# 12V_Analog_Controller.net
KiCad netlist of a schematic drawn in EAGLE
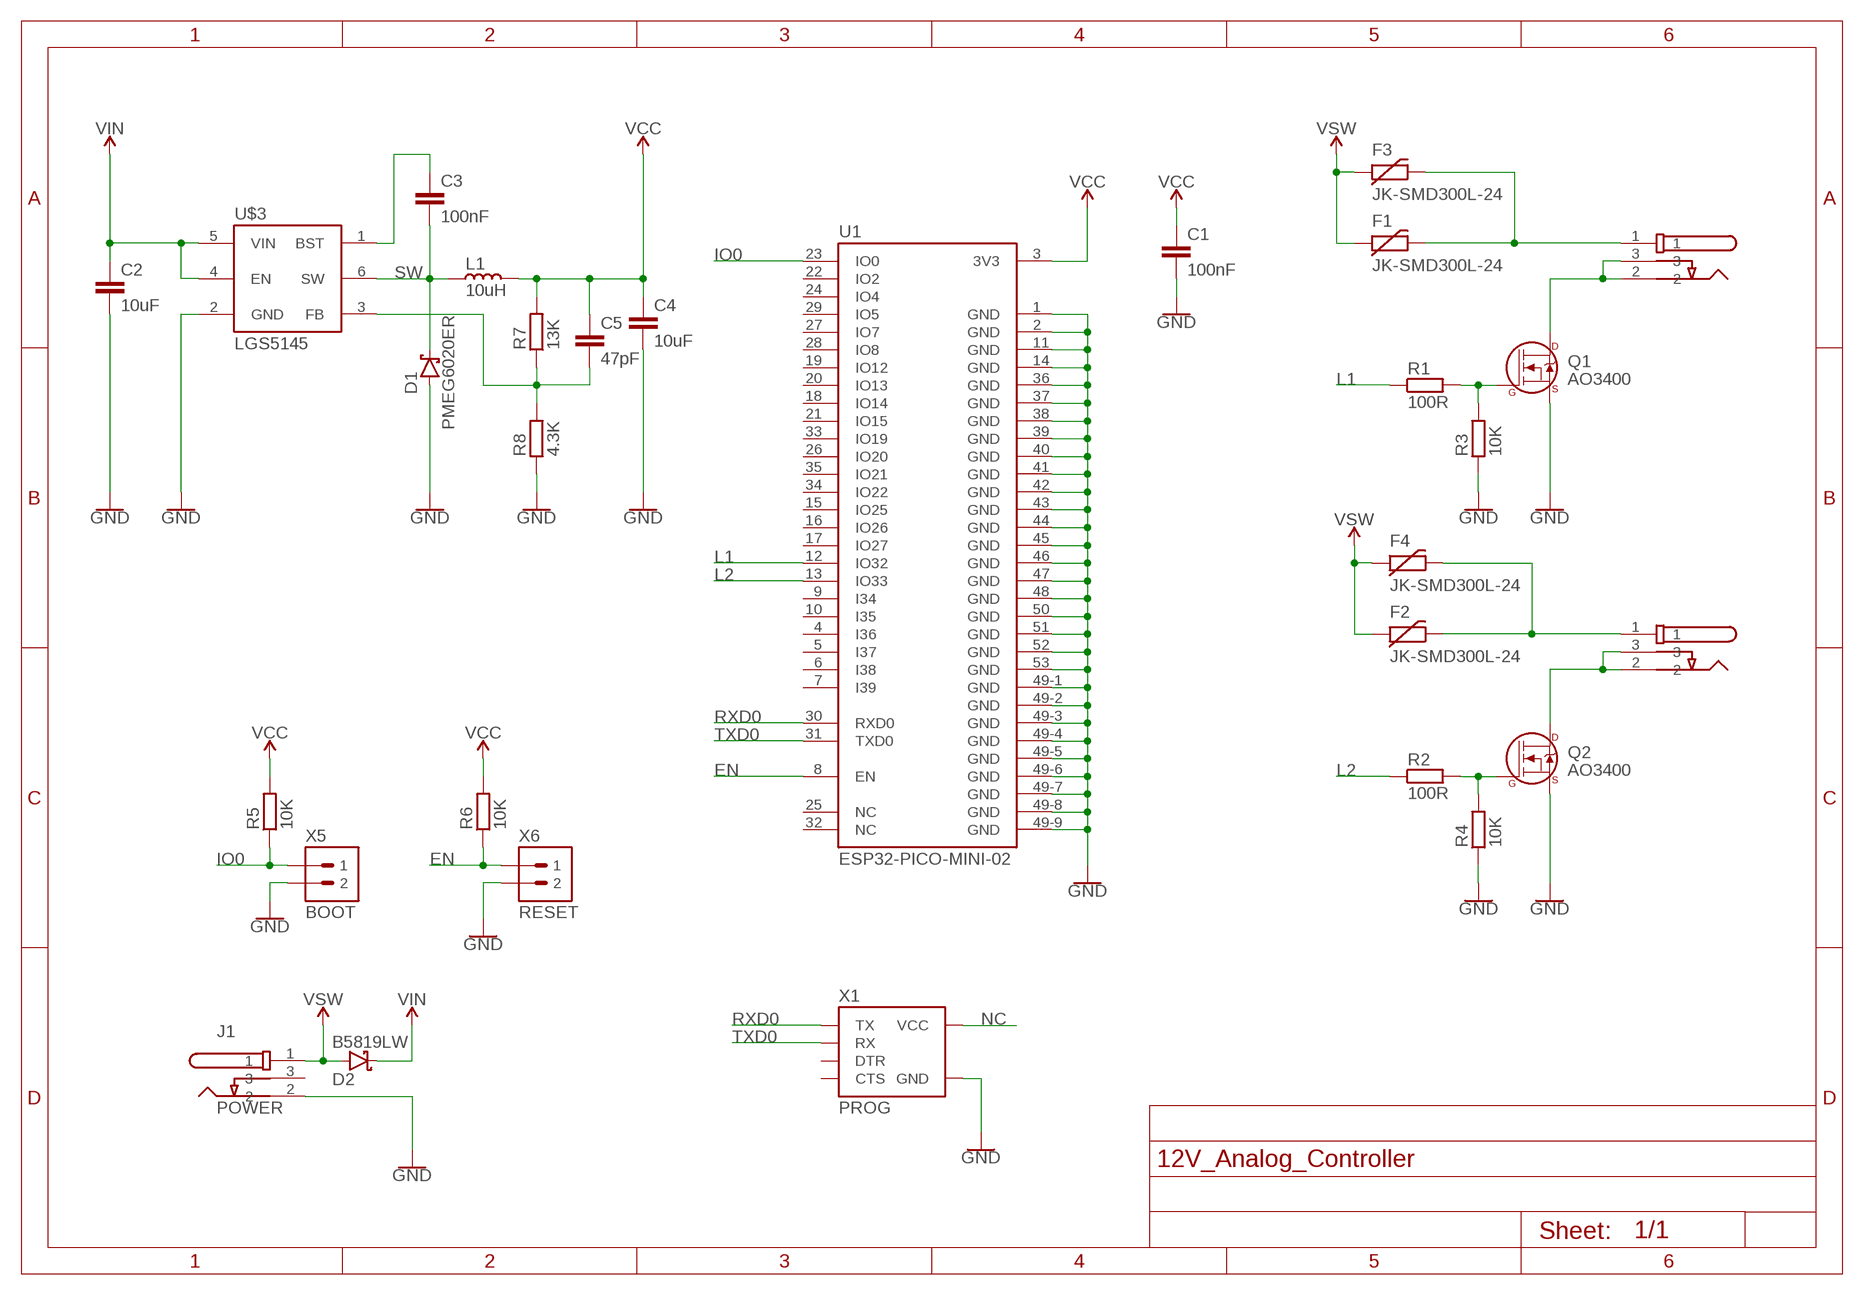
[diagram p0: schematic, sheet 1]

(export (version "E")
  (design (tool "Eeschema 10.0.6"))
  (components
    (comp (ref "C1")
      (value "100nF")
      (footprint "eagle-import:C0603")
      (libsource (lib "eagle-import") (part "CAPC0603"))
    )
    (comp (ref "C2")
      (value "10uF")
      (footprint "eagle-import:C0603")
      (libsource (lib "eagle-import") (part "CAPC0603"))
    )
    (comp (ref "C3")
      (value "100nF")
      (footprint "eagle-import:C0603")
      (libsource (lib "eagle-import") (part "CAPC0603"))
    )
    (comp (ref "C4")
      (value "10uF")
      (footprint "eagle-import:C0603")
      (libsource (lib "eagle-import") (part "CAPC0603"))
    )
    (comp (ref "C5")
      (value "47pF")
      (footprint "eagle-import:C0603")
      (libsource (lib "eagle-import") (part "CAPC0603"))
    )
    (comp (ref "D1")
      (value "PMEG6020ER")
      (footprint "eagle-import:SOD-123FL")
      (libsource (lib "eagle-import") (part "DIODE-SCHOTTKYSOD123FL"))
    )
    (comp (ref "D2")
      (value "B5819LW")
      (footprint "eagle-import:SOD-123")
      (libsource (lib "eagle-import") (part "DIODE-SCHOTTKYSOD-123"))
    )
    (comp (ref "F1")
      (value "JK-SMD300L-24")
      (footprint "eagle-import:JK-SMD300")
      (libsource (lib "eagle-import") (part "PTCJK-SMD300"))
    )
    (comp (ref "F2")
      (value "JK-SMD300L-24")
      (footprint "eagle-import:JK-SMD300")
      (libsource (lib "eagle-import") (part "PTCJK-SMD300"))
    )
    (comp (ref "F3")
      (value "JK-SMD300L-24")
      (footprint "eagle-import:JK-SMD300")
      (libsource (lib "eagle-import") (part "PTCJK-SMD300"))
    )
    (comp (ref "F4")
      (value "JK-SMD300L-24")
      (footprint "eagle-import:JK-SMD300")
      (libsource (lib "eagle-import") (part "PTCJK-SMD300"))
    )
    (comp (ref "J1")
      (value "POWER")
      (footprint "eagle-import:XKB-DC-005-5A-2.0")
      (libsource (lib "eagle-import") (part "XKB-DC-005-5A-2.0"))
    )
    (comp (ref "L1")
      (value "10uH")
      (footprint "eagle-import:YJYCOIN-YNR4062")
      (libsource (lib "eagle-import") (part "IND-YJYCOIN-YNR4062"))
    )
    (comp (ref "Q1")
      (value "AO3400")
      (footprint "eagle-import:SOT23-3")
      (libsource (lib "eagle-import") (part "MOSFET-NCHSOT23-3"))
    )
    (comp (ref "Q2")
      (value "AO3400")
      (footprint "eagle-import:SOT23-3")
      (libsource (lib "eagle-import") (part "MOSFET-NCHSOT23-3"))
    )
    (comp (ref "R1")
      (value "100R")
      (footprint "eagle-import:R0603")
      (libsource (lib "eagle-import") (part "RESISTOR0603"))
    )
    (comp (ref "R2")
      (value "100R")
      (footprint "eagle-import:R0603")
      (libsource (lib "eagle-import") (part "RESISTOR0603"))
    )
    (comp (ref "R3")
      (value "10K")
      (footprint "eagle-import:R0603")
      (libsource (lib "eagle-import") (part "RESISTOR0603"))
    )
    (comp (ref "R4")
      (value "10K")
      (footprint "eagle-import:R0603")
      (libsource (lib "eagle-import") (part "RESISTOR0603"))
    )
    (comp (ref "R5")
      (value "10K")
      (footprint "eagle-import:R0603")
      (libsource (lib "eagle-import") (part "RESISTOR0603"))
    )
    (comp (ref "R6")
      (value "10K")
      (footprint "eagle-import:R0603")
      (libsource (lib "eagle-import") (part "RESISTOR0603"))
    )
    (comp (ref "R7")
      (value "13K")
      (footprint "eagle-import:R0603")
      (libsource (lib "eagle-import") (part "RESISTOR0603"))
    )
    (comp (ref "R8")
      (value "4.3K")
      (footprint "eagle-import:R0603")
      (libsource (lib "eagle-import") (part "RESISTOR0603"))
    )
    (comp (ref "U$3")
      (value "LGS5145")
      (footprint "eagle-import:SOT23-6")
      (libsource (lib "eagle-import") (part "LEGEND-SI-LGS5145"))
    )
    (comp (ref "U1")
      (value "ESP32-PICO-MINI-02")
      (footprint "eagle-import:ESP32-PICO-MINI-02")
      (libsource (lib "eagle-import") (part "ESP32-PICO-MINI-02"))
    )
    (comp (ref "X1")
      (value "PROG")
      (footprint "eagle-import:FTDI232-1X06")
      (libsource (lib "eagle-import") (part "HEADER-FTDI232"))
    )
    (comp (ref "X2")
      (value "L1")
      (footprint "eagle-import:XKB-DC-005-5A-2.0")
      (libsource (lib "eagle-import") (part "XKB-DC-005-5A-2.0"))
    )
    (comp (ref "X3")
      (value "L2")
      (footprint "eagle-import:XKB-DC-005-5A-2.0")
      (libsource (lib "eagle-import") (part "XKB-DC-005-5A-2.0"))
    )
    (comp (ref "X5")
      (value "BOOT")
      (footprint "eagle-import:1X02-2.54")
      (libsource (lib "eagle-import") (part "HEADER-1X02-2.54"))
    )
    (comp (ref "X6")
      (value "RESET")
      (footprint "eagle-import:1X02-2.54")
      (libsource (lib "eagle-import") (part "HEADER-1X02-2.54"))
    )
  )
  (nets
    (net (code "1") (name "/EN") (class "Default")
      (node (ref "R6") (pin "1") (pinfunction "1_1") (pintype "passive"))
      (node (ref "U1") (pin "8") (pinfunction "EN_8") (pintype "bidirectional"))
      (node (ref "X6") (pin "1") (pinfunction "1_1") (pintype "passive"))
    )
    (net (code "2") (name "/IO0") (class "Default")
      (node (ref "R5") (pin "1") (pinfunction "1_1") (pintype "passive"))
      (node (ref "U1") (pin "23") (pinfunction "IO0_23") (pintype "bidirectional"))
      (node (ref "X5") (pin "1") (pinfunction "1_1") (pintype "passive"))
    )
    (net (code "3") (name "/L1") (class "Default")
      (node (ref "R1") (pin "1") (pinfunction "1_1") (pintype "passive"))
      (node (ref "U1") (pin "12") (pinfunction "IO32_12") (pintype "bidirectional"))
    )
    (net (code "4") (name "/L2") (class "Default")
      (node (ref "R2") (pin "1") (pinfunction "1_1") (pintype "passive"))
      (node (ref "U1") (pin "13") (pinfunction "IO33_13") (pintype "bidirectional"))
    )
    (net (code "5") (name "/NC") (class "Default")
      (node (ref "X1") (pin "VCC") (pinfunction "VCC_VCC") (pintype "power_in"))
    )
    (net (code "6") (name "/RXD0") (class "Default")
      (node (ref "U1") (pin "30") (pinfunction "RXD0_30") (pintype "bidirectional"))
      (node (ref "X1") (pin "TX") (pinfunction "TX_TX") (pintype "output"))
    )
    (net (code "7") (name "/SW") (class "Default")
      (node (ref "C3") (pin "2") (pinfunction "2_2") (pintype "passive"))
      (node (ref "D1") (pin "C") (pinfunction "C_C") (pintype "passive"))
      (node (ref "L1") (pin "1") (pinfunction "1_1") (pintype "passive"))
      (node (ref "U$3") (pin "6") (pinfunction "SW_6") (pintype "bidirectional"))
    )
    (net (code "8") (name "/TXD0") (class "Default")
      (node (ref "U1") (pin "31") (pinfunction "TXD0_31") (pintype "bidirectional"))
      (node (ref "X1") (pin "RX") (pinfunction "RX_RX") (pintype "input"))
    )
    (net (code "9") (name "GND") (class "Default")
      (node (ref "C1") (pin "2") (pinfunction "2_2") (pintype "passive"))
      (node (ref "C2") (pin "2") (pinfunction "2_2") (pintype "passive"))
      (node (ref "C4") (pin "2") (pinfunction "2_2") (pintype "passive"))
      (node (ref "D1") (pin "A") (pinfunction "A_A") (pintype "passive"))
      (node (ref "J1") (pin "2") (pinfunction "2_2") (pintype "bidirectional"))
      (node (ref "Q1") (pin "2") (pinfunction "S_2") (pintype "bidirectional"))
      (node (ref "Q2") (pin "2") (pinfunction "S_2") (pintype "bidirectional"))
      (node (ref "R3") (pin "1") (pinfunction "1_1") (pintype "passive"))
      (node (ref "R4") (pin "1") (pinfunction "1_1") (pintype "passive"))
      (node (ref "R8") (pin "1") (pinfunction "1_1") (pintype "passive"))
      (node (ref "U$3") (pin "2") (pinfunction "GND_2") (pintype "bidirectional"))
      (node (ref "U1") (pin "1") (pinfunction "GND_1") (pintype "bidirectional"))
      (node (ref "U1") (pin "11") (pinfunction "GND_11") (pintype "bidirectional"))
      (node (ref "U1") (pin "14") (pinfunction "GND_14") (pintype "bidirectional"))
      (node (ref "U1") (pin "2") (pinfunction "GND_2") (pintype "bidirectional"))
      (node (ref "U1") (pin "36") (pinfunction "GND_36") (pintype "bidirectional"))
      (node (ref "U1") (pin "37") (pinfunction "GND_37") (pintype "bidirectional"))
      (node (ref "U1") (pin "38") (pinfunction "GND_38") (pintype "bidirectional"))
      (node (ref "U1") (pin "39") (pinfunction "GND_39") (pintype "bidirectional"))
      (node (ref "U1") (pin "40") (pinfunction "GND_40") (pintype "bidirectional"))
      (node (ref "U1") (pin "41") (pinfunction "GND_41") (pintype "bidirectional"))
      (node (ref "U1") (pin "42") (pinfunction "GND_42") (pintype "bidirectional"))
      (node (ref "U1") (pin "43") (pinfunction "GND_43") (pintype "bidirectional"))
      (node (ref "U1") (pin "44") (pinfunction "GND_44") (pintype "bidirectional"))
      (node (ref "U1") (pin "45") (pinfunction "GND_45") (pintype "bidirectional"))
      (node (ref "U1") (pin "46") (pinfunction "GND_46") (pintype "bidirectional"))
      (node (ref "U1") (pin "47") (pinfunction "GND_47") (pintype "bidirectional"))
      (node (ref "U1") (pin "48") (pinfunction "GND_48") (pintype "bidirectional"))
      (node (ref "U1") (pin "49-1") (pinfunction "GND_49-1") (pintype "bidirectional"))
      (node (ref "U1") (pin "49-2") (pinfunction "GND_49-2") (pintype "bidirectional"))
      (node (ref "U1") (pin "49-3") (pinfunction "GND_49-3") (pintype "bidirectional"))
      (node (ref "U1") (pin "49-4") (pinfunction "GND_49-4") (pintype "bidirectional"))
      (node (ref "U1") (pin "49-5") (pinfunction "GND_49-5") (pintype "bidirectional"))
      (node (ref "U1") (pin "49-6") (pinfunction "GND_49-6") (pintype "bidirectional"))
      (node (ref "U1") (pin "49-7") (pinfunction "GND_49-7") (pintype "bidirectional"))
      (node (ref "U1") (pin "49-8") (pinfunction "GND_49-8") (pintype "bidirectional"))
      (node (ref "U1") (pin "49-9") (pinfunction "GND_49-9") (pintype "bidirectional"))
      (node (ref "U1") (pin "50") (pinfunction "GND_50") (pintype "bidirectional"))
      (node (ref "U1") (pin "51") (pinfunction "GND_51") (pintype "bidirectional"))
      (node (ref "U1") (pin "52") (pinfunction "GND_52") (pintype "bidirectional"))
      (node (ref "U1") (pin "53") (pinfunction "GND_53") (pintype "bidirectional"))
      (node (ref "X1") (pin "GND") (pinfunction "GND_GND") (pintype "power_in"))
      (node (ref "X5") (pin "2") (pinfunction "2_2") (pintype "passive"))
      (node (ref "X6") (pin "2") (pinfunction "2_2") (pintype "passive"))
    )
    (net (code "10") (name "Net-(F1-2)") (class "Default")
      (node (ref "F1") (pin "B") (pinfunction "2_B") (pintype "bidirectional"))
      (node (ref "F3") (pin "B") (pinfunction "2_B") (pintype "bidirectional"))
      (node (ref "X2") (pin "1") (pinfunction "1_1") (pintype "bidirectional"))
    )
    (net (code "11") (name "Net-(F2-2)") (class "Default")
      (node (ref "F2") (pin "B") (pinfunction "2_B") (pintype "bidirectional"))
      (node (ref "F4") (pin "B") (pinfunction "2_B") (pintype "bidirectional"))
      (node (ref "X3") (pin "1") (pinfunction "1_1") (pintype "bidirectional"))
    )
    (net (code "12") (name "Net-(Q1-D)") (class "Default")
      (node (ref "Q1") (pin "3") (pinfunction "D_3") (pintype "bidirectional"))
      (node (ref "X2") (pin "2") (pinfunction "2_2") (pintype "bidirectional"))
      (node (ref "X2") (pin "3") (pinfunction "3_3") (pintype "bidirectional"))
    )
    (net (code "13") (name "Net-(Q1-G)") (class "Default")
      (node (ref "Q1") (pin "1") (pinfunction "G_1") (pintype "bidirectional"))
      (node (ref "R1") (pin "2") (pinfunction "2_2") (pintype "passive"))
      (node (ref "R3") (pin "2") (pinfunction "2_2") (pintype "passive"))
    )
    (net (code "14") (name "Net-(Q2-D)") (class "Default")
      (node (ref "Q2") (pin "3") (pinfunction "D_3") (pintype "bidirectional"))
      (node (ref "X3") (pin "2") (pinfunction "2_2") (pintype "bidirectional"))
      (node (ref "X3") (pin "3") (pinfunction "3_3") (pintype "bidirectional"))
    )
    (net (code "15") (name "Net-(Q2-G)") (class "Default")
      (node (ref "Q2") (pin "1") (pinfunction "G_1") (pintype "bidirectional"))
      (node (ref "R2") (pin "2") (pinfunction "2_2") (pintype "passive"))
      (node (ref "R4") (pin "2") (pinfunction "2_2") (pintype "passive"))
    )
    (net (code "16") (name "Net-(U$3-BST)") (class "Default")
      (node (ref "C3") (pin "1") (pinfunction "1_1") (pintype "passive"))
      (node (ref "U$3") (pin "1") (pinfunction "BST_1") (pintype "bidirectional"))
    )
    (net (code "17") (name "Net-(U$3-FB)") (class "Default")
      (node (ref "C5") (pin "2") (pinfunction "2_2") (pintype "passive"))
      (node (ref "R7") (pin "1") (pinfunction "1_1") (pintype "passive"))
      (node (ref "R8") (pin "2") (pinfunction "2_2") (pintype "passive"))
      (node (ref "U$3") (pin "3") (pinfunction "FB_3") (pintype "bidirectional"))
    )
    (net (code "18") (name "VCC") (class "Default")
      (node (ref "C1") (pin "1") (pinfunction "1_1") (pintype "passive"))
      (node (ref "C4") (pin "1") (pinfunction "1_1") (pintype "passive"))
      (node (ref "C5") (pin "1") (pinfunction "1_1") (pintype "passive"))
      (node (ref "L1") (pin "2") (pinfunction "2_2") (pintype "passive"))
      (node (ref "R5") (pin "2") (pinfunction "2_2") (pintype "passive"))
      (node (ref "R6") (pin "2") (pinfunction "2_2") (pintype "passive"))
      (node (ref "R7") (pin "2") (pinfunction "2_2") (pintype "passive"))
      (node (ref "U1") (pin "3") (pinfunction "3V3_3") (pintype "bidirectional"))
    )
    (net (code "19") (name "VIN") (class "Default")
      (node (ref "C2") (pin "1") (pinfunction "1_1") (pintype "passive"))
      (node (ref "D2") (pin "C") (pinfunction "C_C") (pintype "passive"))
      (node (ref "U$3") (pin "4") (pinfunction "EN_4") (pintype "bidirectional"))
      (node (ref "U$3") (pin "5") (pinfunction "VIN_5") (pintype "bidirectional"))
    )
    (net (code "20") (name "VSW") (class "Default")
      (node (ref "D2") (pin "A") (pinfunction "A_A") (pintype "passive"))
      (node (ref "F1") (pin "A") (pinfunction "1_A") (pintype "bidirectional"))
      (node (ref "F2") (pin "A") (pinfunction "1_A") (pintype "bidirectional"))
      (node (ref "F3") (pin "A") (pinfunction "1_A") (pintype "bidirectional"))
      (node (ref "F4") (pin "A") (pinfunction "1_A") (pintype "bidirectional"))
      (node (ref "J1") (pin "1") (pinfunction "1_1") (pintype "bidirectional"))
    )
    (net (code "21") (name "unconnected-(J1-Pad3)") (class "Default")
      (node (ref "J1") (pin "3") (pinfunction "3_3") (pintype "bidirectional"))
    )
    (net (code "22") (name "unconnected-(U1-I34-Pad9)") (class "Default")
      (node (ref "U1") (pin "9") (pinfunction "I34_9") (pintype "bidirectional"))
    )
    (net (code "23") (name "unconnected-(U1-I35-Pad10)") (class "Default")
      (node (ref "U1") (pin "10") (pinfunction "I35_10") (pintype "bidirectional"))
    )
    (net (code "24") (name "unconnected-(U1-I36-Pad4)") (class "Default")
      (node (ref "U1") (pin "4") (pinfunction "I36_4") (pintype "bidirectional"))
    )
    (net (code "25") (name "unconnected-(U1-I37-Pad5)") (class "Default")
      (node (ref "U1") (pin "5") (pinfunction "I37_5") (pintype "bidirectional"))
    )
    (net (code "26") (name "unconnected-(U1-I38-Pad6)") (class "Default")
      (node (ref "U1") (pin "6") (pinfunction "I38_6") (pintype "bidirectional"))
    )
    (net (code "27") (name "unconnected-(U1-I39-Pad7)") (class "Default")
      (node (ref "U1") (pin "7") (pinfunction "I39_7") (pintype "bidirectional"))
    )
    (net (code "28") (name "unconnected-(U1-IO2-Pad22)") (class "Default")
      (node (ref "U1") (pin "22") (pinfunction "IO2_22") (pintype "bidirectional"))
    )
    (net (code "29") (name "unconnected-(U1-IO4-Pad24)") (class "Default")
      (node (ref "U1") (pin "24") (pinfunction "IO4_24") (pintype "bidirectional"))
    )
    (net (code "30") (name "unconnected-(U1-IO5-Pad29)") (class "Default")
      (node (ref "U1") (pin "29") (pinfunction "IO5_29") (pintype "bidirectional"))
    )
    (net (code "31") (name "unconnected-(U1-IO7-Pad27)") (class "Default")
      (node (ref "U1") (pin "27") (pinfunction "IO7_27") (pintype "bidirectional"))
    )
    (net (code "32") (name "unconnected-(U1-IO8-Pad28)") (class "Default")
      (node (ref "U1") (pin "28") (pinfunction "IO8_28") (pintype "bidirectional"))
    )
    (net (code "33") (name "unconnected-(U1-IO12-Pad19)") (class "Default")
      (node (ref "U1") (pin "19") (pinfunction "IO12_19") (pintype "bidirectional"))
    )
    (net (code "34") (name "unconnected-(U1-IO13-Pad20)") (class "Default")
      (node (ref "U1") (pin "20") (pinfunction "IO13_20") (pintype "bidirectional"))
    )
    (net (code "35") (name "unconnected-(U1-IO14-Pad18)") (class "Default")
      (node (ref "U1") (pin "18") (pinfunction "IO14_18") (pintype "bidirectional"))
    )
    (net (code "36") (name "unconnected-(U1-IO15-Pad21)") (class "Default")
      (node (ref "U1") (pin "21") (pinfunction "IO15_21") (pintype "bidirectional"))
    )
    (net (code "37") (name "unconnected-(U1-IO19-Pad33)") (class "Default")
      (node (ref "U1") (pin "33") (pinfunction "IO19_33") (pintype "bidirectional"))
    )
    (net (code "38") (name "unconnected-(U1-IO20-Pad26)") (class "Default")
      (node (ref "U1") (pin "26") (pinfunction "IO20_26") (pintype "bidirectional"))
    )
    (net (code "39") (name "unconnected-(U1-IO21-Pad35)") (class "Default")
      (node (ref "U1") (pin "35") (pinfunction "IO21_35") (pintype "bidirectional"))
    )
    (net (code "40") (name "unconnected-(U1-IO22-Pad34)") (class "Default")
      (node (ref "U1") (pin "34") (pinfunction "IO22_34") (pintype "bidirectional"))
    )
    (net (code "41") (name "unconnected-(U1-IO25-Pad15)") (class "Default")
      (node (ref "U1") (pin "15") (pinfunction "IO25_15") (pintype "bidirectional"))
    )
    (net (code "42") (name "unconnected-(U1-IO26-Pad16)") (class "Default")
      (node (ref "U1") (pin "16") (pinfunction "IO26_16") (pintype "bidirectional"))
    )
    (net (code "43") (name "unconnected-(U1-IO27-Pad17)") (class "Default")
      (node (ref "U1") (pin "17") (pinfunction "IO27_17") (pintype "bidirectional"))
    )
    (net (code "44") (name "unconnected-(U1-NC-Pad25)") (class "Default")
      (node (ref "U1") (pin "25") (pinfunction "NC_25") (pintype "bidirectional"))
    )
    (net (code "45") (name "unconnected-(U1-NC-Pad32)") (class "Default")
      (node (ref "U1") (pin "32") (pinfunction "NC_32") (pintype "bidirectional"))
    )
    (net (code "46") (name "unconnected-(X1-PadCTS)") (class "Default")
      (node (ref "X1") (pin "CTS") (pinfunction "CTS_CTS") (pintype "output"))
    )
    (net (code "47") (name "unconnected-(X1-PadDTR)") (class "Default")
      (node (ref "X1") (pin "DTR") (pinfunction "DTR_DTR") (pintype "output"))
    )
  )
)
